# ProximityDetector.net
KiCad netlist of a schematic drawn in Altium Designer
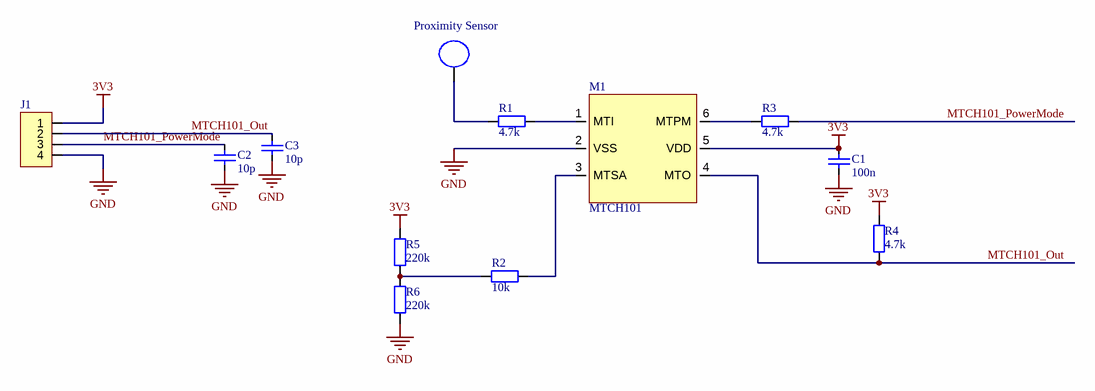
[diagram p0: ProximityDetector.SchDoc]

(export (version "E")
  (design (tool "Eeschema 10.0.6"))
  (components
    (comp (ref "C1")
      (value "100n")
      (footprint "0805_C")
      (description "Cap")
      (libsource (lib "Sch_Lib") (part "Cap"))
    )
    (comp (ref "C2")
      (value "10p")
      (footprint "0805_C")
      (description "Cap")
      (libsource (lib "Sch_Lib") (part "Cap"))
    )
    (comp (ref "C3")
      (value "10p")
      (footprint "0805_C")
      (description "Cap")
      (libsource (lib "Sch_Lib") (part "Cap"))
    )
    (comp (ref "J1") (value "~") (footprint "CON_THT_4P_RM2.54") (libsource (lib "Sch_Lib") (part "CON_4P")))
    (comp (ref "M1")
      (value "MTCH101")
      (footprint "SOT23-6")
      (libsource (lib "ProximityDetector") (part "MTCH101"))
    )
    (comp (ref "Proximity Sensor")
      (value "Detector")
      (footprint "Hole_1.3mm")
      (libsource (lib "ProximityDetector_1") (part "Detector"))
    )
    (comp (ref "R1")
      (value "4.7k")
      (footprint "0805_R")
      (description "Res")
      (libsource (lib "") (part "Res_1"))
    )
    (comp (ref "R2")
      (value "10k")
      (footprint "0805_R")
      (description "Res")
      (libsource (lib "") (part "Res_1"))
    )
    (comp (ref "R3")
      (value "4.7k")
      (footprint "0805_R")
      (description "Res")
      (libsource (lib "") (part "Res_1"))
    )
    (comp (ref "R4")
      (value "4.7k")
      (footprint "0805_R")
      (description "Res")
      (libsource (lib "Sch_Lib") (part "Res"))
    )
    (comp (ref "R5")
      (value "220k")
      (footprint "0805_R")
      (description "Res")
      (libsource (lib "Sch_Lib") (part "Res"))
    )
    (comp (ref "R6")
      (value "220k")
      (footprint "0805_R")
      (description "Res")
      (libsource (lib "Sch_Lib") (part "Res"))
    )
  )
  (nets
    (net (code "1") (name "/MTCH101_Out") (class "Default")
      (node (ref "C3") (pin "2") (pinfunction "2_2") (pintype "passive"))
      (node (ref "J1") (pin "2") (pinfunction "2_2") (pintype "passive"))
      (node (ref "M1") (pin "4") (pinfunction "MTO_4") (pintype "passive"))
      (node (ref "R4") (pin "1") (pinfunction "1_1") (pintype "passive"))
    )
    (net (code "2") (name "/MTCH101_PowerMode") (class "Default")
      (node (ref "C2") (pin "2") (pinfunction "2_2") (pintype "passive"))
      (node (ref "J1") (pin "3") (pinfunction "3_3") (pintype "passive"))
      (node (ref "R3") (pin "2") (pinfunction "2_2") (pintype "passive"))
    )
    (net (code "3") (name "3V3") (class "Default")
      (node (ref "C1") (pin "2") (pinfunction "2_2") (pintype "passive"))
      (node (ref "J1") (pin "1") (pinfunction "1_1") (pintype "passive"))
      (node (ref "M1") (pin "5") (pinfunction "VDD_5") (pintype "passive"))
      (node (ref "R4") (pin "2") (pinfunction "2_2") (pintype "passive"))
      (node (ref "R5") (pin "2") (pinfunction "2_2") (pintype "passive"))
    )
    (net (code "4") (name "GND") (class "Default")
      (node (ref "C1") (pin "1") (pinfunction "1_1") (pintype "passive"))
      (node (ref "C2") (pin "1") (pinfunction "1_1") (pintype "passive"))
      (node (ref "C3") (pin "1") (pinfunction "1_1") (pintype "passive"))
      (node (ref "J1") (pin "4") (pinfunction "4_4") (pintype "passive"))
      (node (ref "M1") (pin "2") (pinfunction "VSS_2") (pintype "passive"))
      (node (ref "R6") (pin "1") (pinfunction "1_1") (pintype "passive"))
    )
    (net (code "5") (name "Net-(M1-MTI)") (class "Default")
      (node (ref "M1") (pin "1") (pinfunction "MTI_1") (pintype "passive"))
      (node (ref "R1") (pin "2") (pinfunction "2_2") (pintype "passive"))
    )
    (net (code "6") (name "Net-(M1-MTPM)") (class "Default")
      (node (ref "M1") (pin "6") (pinfunction "MTPM_6") (pintype "passive"))
      (node (ref "R3") (pin "1") (pinfunction "1_1") (pintype "passive"))
    )
    (net (code "7") (name "Net-(M1-MTSA)") (class "Default")
      (node (ref "M1") (pin "3") (pinfunction "MTSA_3") (pintype "passive"))
      (node (ref "R2") (pin "2") (pinfunction "2_2") (pintype "passive"))
    )
    (net (code "8") (name "Net-(Proximity Sensor-Pad1)") (class "Default")
      (node (ref "Proximity Sensor") (pin "1") (pintype "passive"))
      (node (ref "R1") (pin "1") (pinfunction "1_1") (pintype "passive"))
    )
    (net (code "9") (name "Net-(R2-Pad1)") (class "Default")
      (node (ref "R2") (pin "1") (pinfunction "1_1") (pintype "passive"))
      (node (ref "R5") (pin "1") (pinfunction "1_1") (pintype "passive"))
      (node (ref "R6") (pin "2") (pinfunction "2_2") (pintype "passive"))
    )
  )
)
